# 1-Schematic_PCB1.net
KiCad netlist of a schematic drawn in EasyEDA
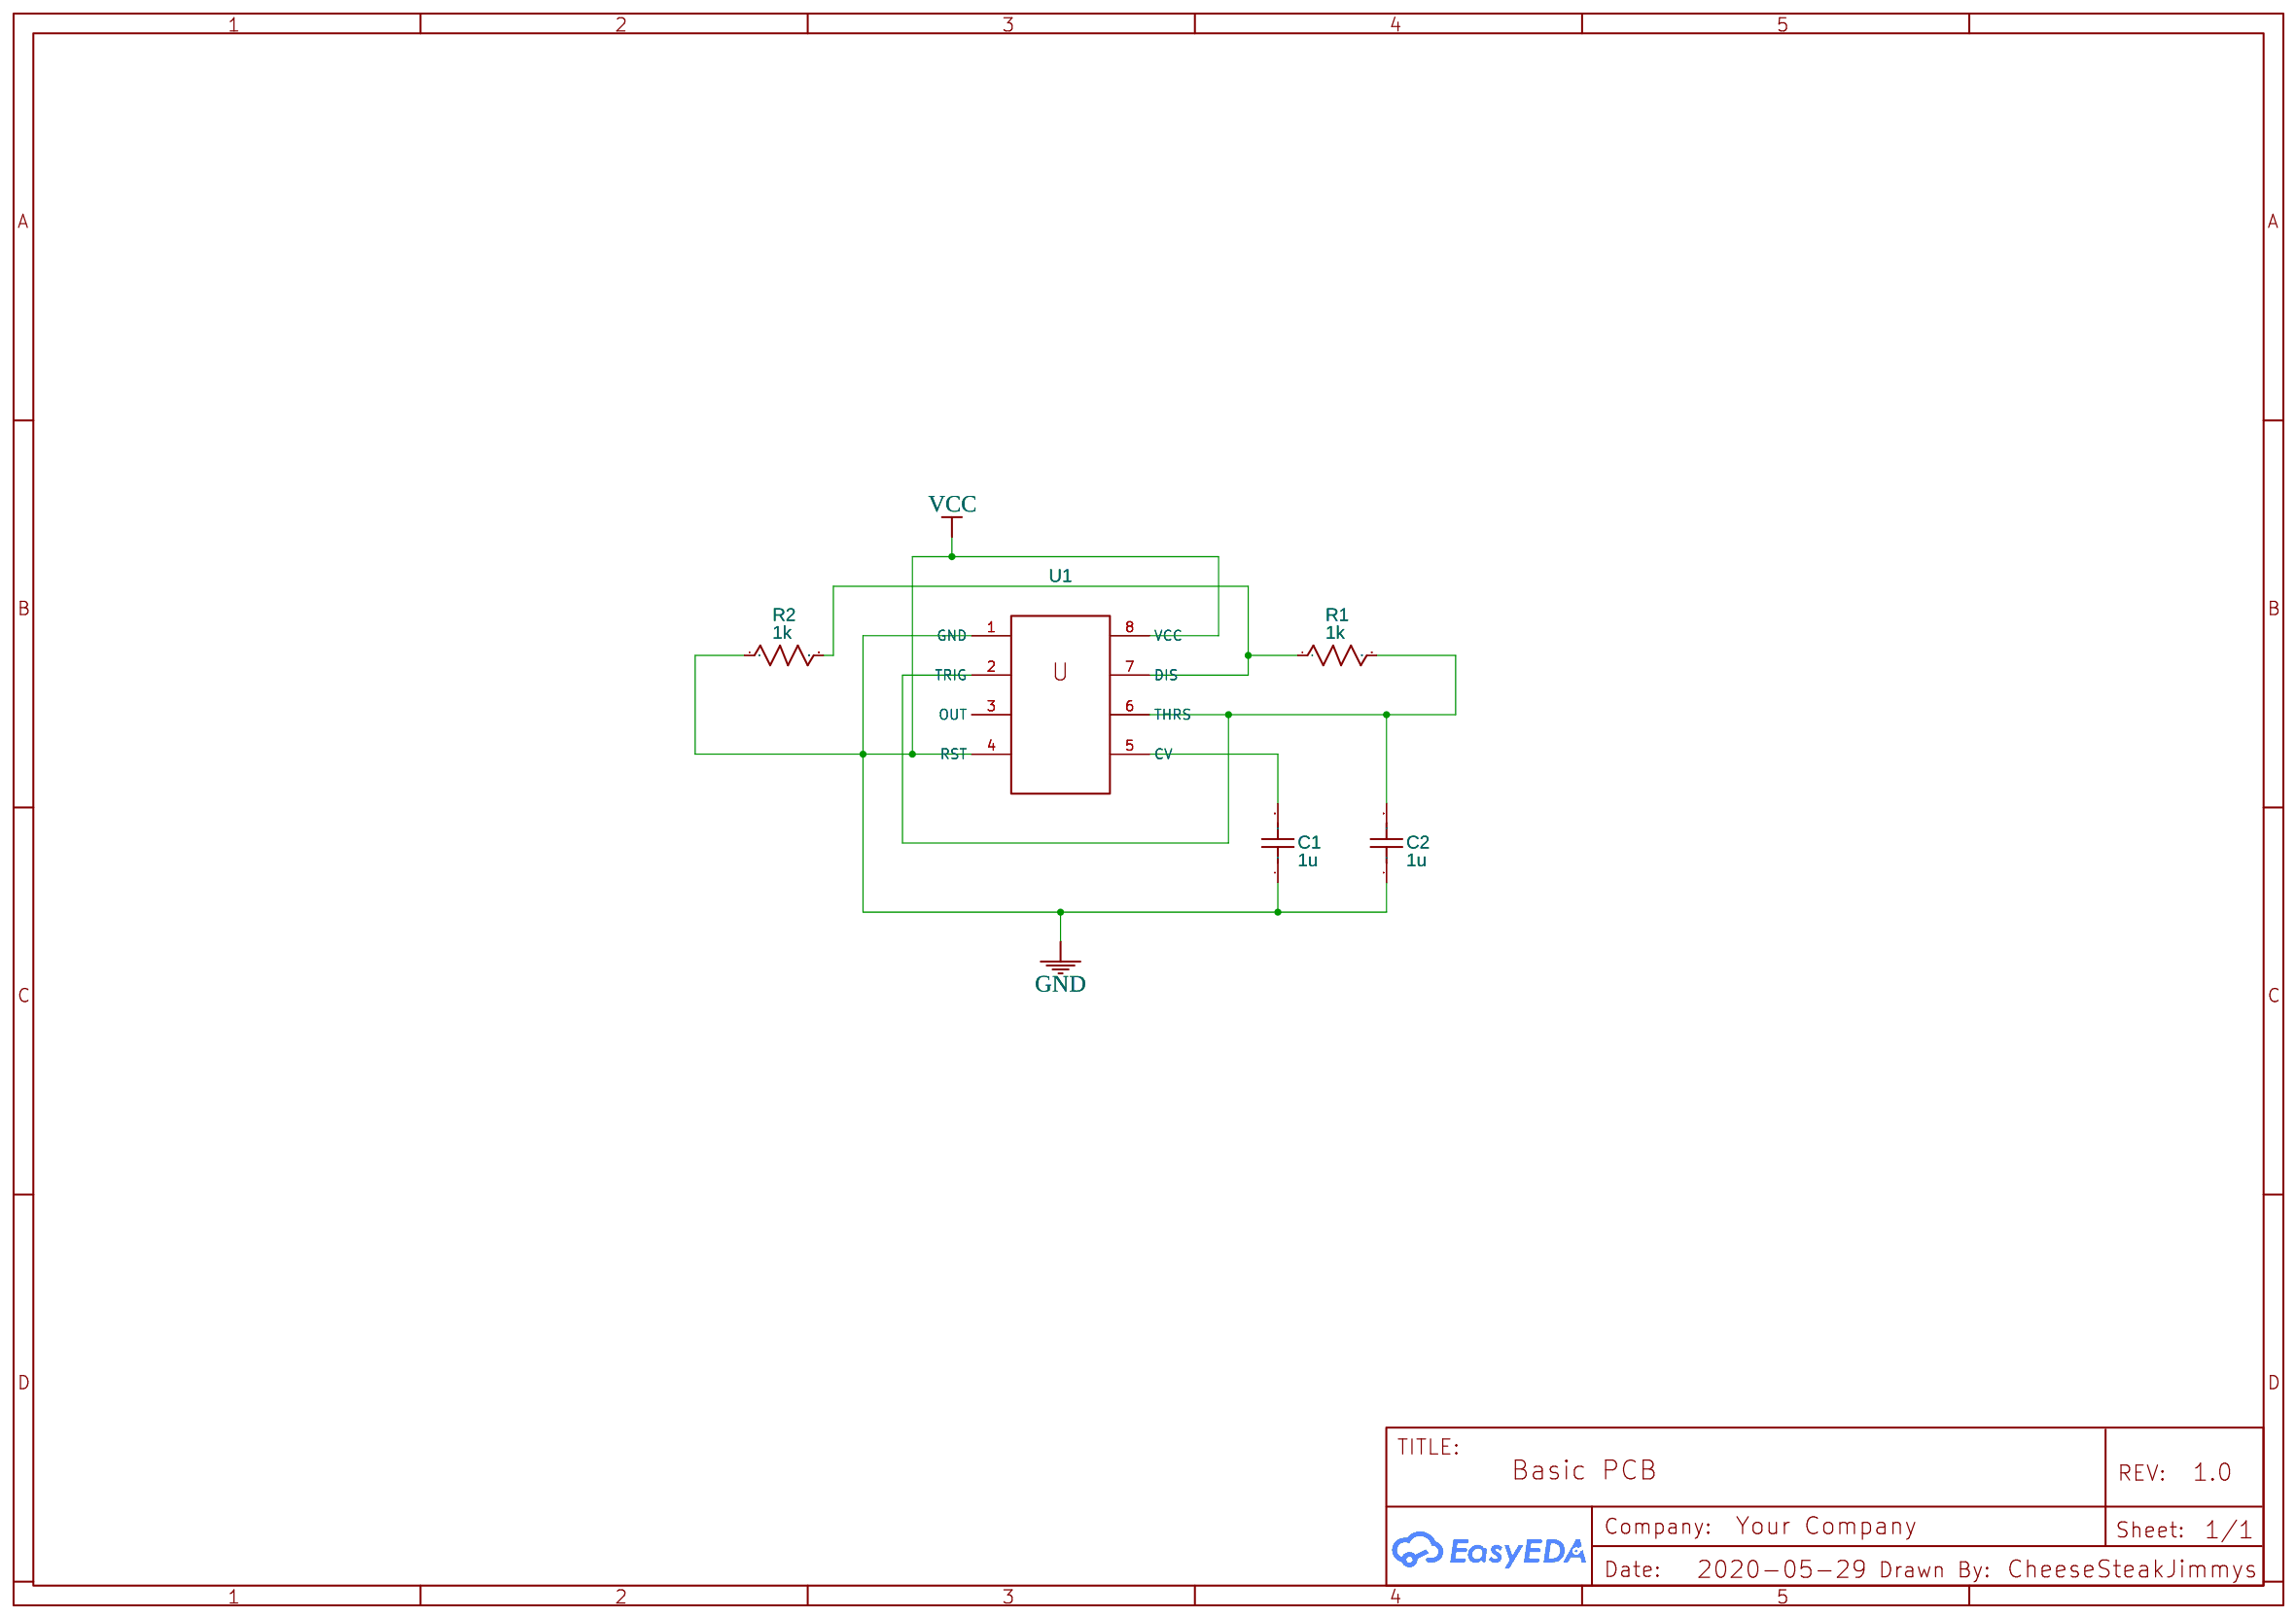
[diagram p0: schematic sheet]

(export (version "E")
  (design (tool "Eeschema 10.0.6"))
  (components
    (comp (ref "C1") (value "1u") (libsource (lib "") (part "C_0201_US")))
    (comp (ref "C2") (value "1u") (libsource (lib "") (part "C_0201_US")))
    (comp (ref "R1") (value "1k") (libsource (lib "") (part "R_0201_US")))
    (comp (ref "R2") (value "1k") (libsource (lib "") (part "R_0201_US")))
    (comp (ref "U1")
      (value "U1")
      (fields (field (name "BOM_Supplier Part") "undefined"))
      (libsource (lib "") (part "U1"))
    )
  )
  (nets
    (net (code "1") (name "GND") (class "Default")
      (node (ref "C1") (pin "1") (pinfunction "1_1") (pintype "unspecified"))
      (node (ref "C2") (pin "1") (pinfunction "1_1") (pintype "unspecified"))
      (node (ref "R2") (pin "1") (pinfunction "1_1") (pintype "unspecified"))
      (node (ref "U1") (pin "1") (pinfunction "GND_1") (pintype "unspecified"))
      (node (ref "U1") (pin "4") (pinfunction "RST_4") (pintype "unspecified"))
      (node (ref "U1") (pin "8") (pinfunction "VCC_8") (pintype "unspecified"))
    )
    (net (code "2") (name "Net-(U1-CV)") (class "Default")
      (node (ref "C1") (pin "2") (pinfunction "2_2") (pintype "unspecified"))
      (node (ref "U1") (pin "5") (pinfunction "CV_5") (pintype "unspecified"))
    )
    (net (code "3") (name "Net-(U1-DIS)") (class "Default")
      (node (ref "R1") (pin "1") (pinfunction "1_1") (pintype "unspecified"))
      (node (ref "R2") (pin "2") (pinfunction "2_2") (pintype "unspecified"))
      (node (ref "U1") (pin "7") (pinfunction "DIS_7") (pintype "unspecified"))
    )
    (net (code "4") (name "Net-(U1-THRS)") (class "Default")
      (node (ref "C2") (pin "2") (pinfunction "2_2") (pintype "unspecified"))
      (node (ref "R1") (pin "2") (pinfunction "2_2") (pintype "unspecified"))
      (node (ref "U1") (pin "2") (pinfunction "TRIG_2") (pintype "unspecified"))
      (node (ref "U1") (pin "6") (pinfunction "THRS_6") (pintype "unspecified"))
    )
    (net (code "5") (name "unconnected-(U1-OUT-Pad3)") (class "Default")
      (node (ref "U1") (pin "3") (pinfunction "OUT_3") (pintype "unspecified"))
    )
  )
)
